# Y-babies_ATtiny84--_PRINT_VER.net
KiCad netlist of a schematic drawn in EAGLE
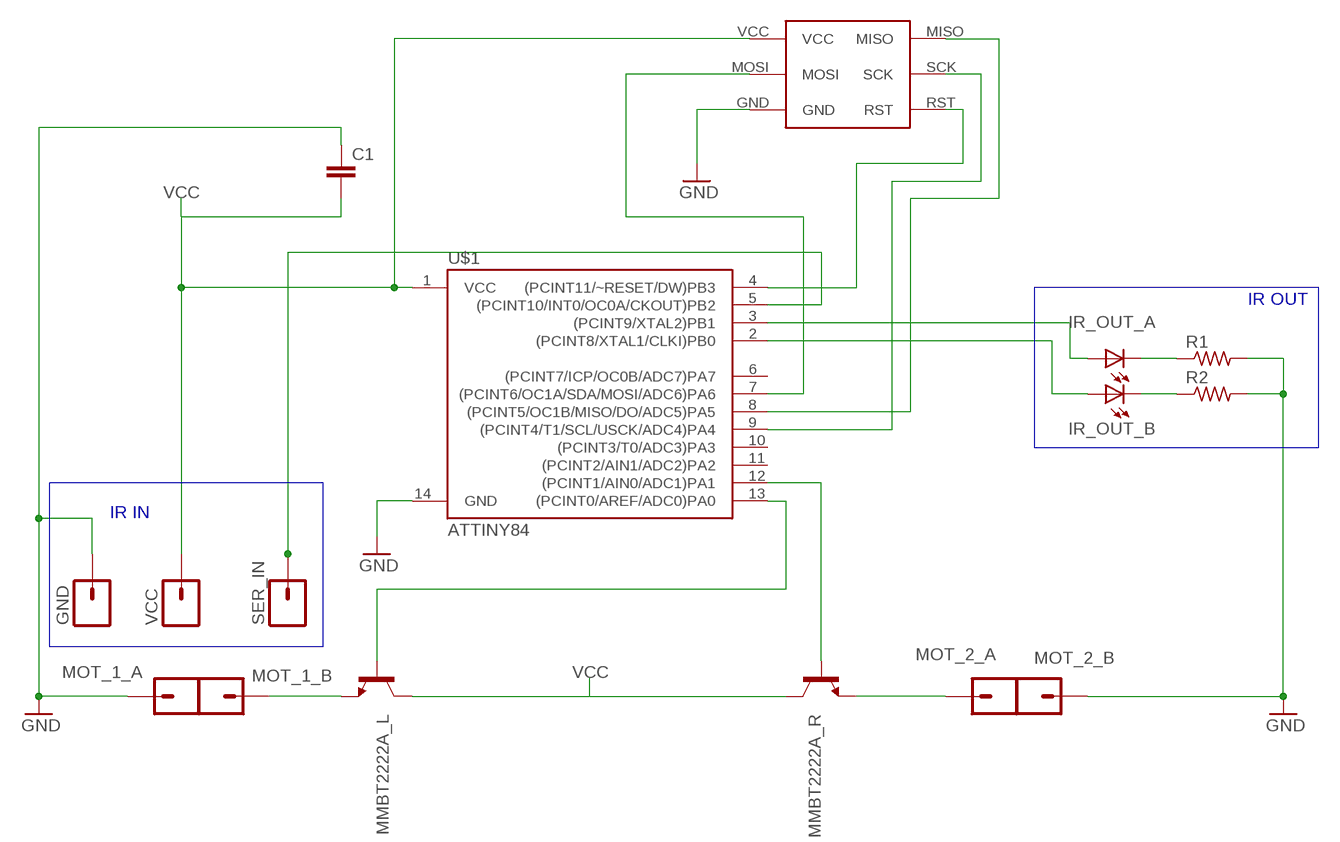
[diagram p0: schematic, sheet 1]

(export (version "E")
  (design (tool "Eeschema 10.0.6"))
  (components
    (comp (ref "C1")
      (value "CAPSMD")
      (footprint "eagle-import:GRM43D")
      (libsource (lib "eagle-import") (part "CAPSMD"))
    )
    (comp (ref "GND")
      (value "M01PTH")
      (footprint "eagle-import:1X01")
      (libsource (lib "eagle-import") (part "M01PTH"))
    )
    (comp (ref "IR_OUT_A")
      (value "LED3MM")
      (footprint "eagle-import:LED3MM")
      (libsource (lib "eagle-import") (part "LED3MM"))
    )
    (comp (ref "IR_OUT_B")
      (value "LED3MM")
      (footprint "eagle-import:LED3MM")
      (libsource (lib "eagle-import") (part "LED3MM"))
    )
    (comp (ref "MMBT2222A_L")
      (value "TRANSISTOR_NPNSOT23")
      (footprint "eagle-import:SOT23")
      (libsource (lib "eagle-import") (part "TRANSISTOR_NPNSOT23"))
    )
    (comp (ref "MMBT2222A_R")
      (value "TRANSISTOR_NPNSOT23")
      (footprint "eagle-import:SOT23")
      (libsource (lib "eagle-import") (part "TRANSISTOR_NPNSOT23"))
    )
    (comp (ref "MOT_1_A")
      (value "M01SMD-4.5X1.5")
      (footprint "eagle-import:PAD-1.5X4.5")
      (libsource (lib "eagle-import") (part "M01SMD-4.5X1.5"))
    )
    (comp (ref "MOT_1_B")
      (value "M01SMD-4.5X1.5")
      (footprint "eagle-import:PAD-1.5X4.5")
      (libsource (lib "eagle-import") (part "M01SMD-4.5X1.5"))
    )
    (comp (ref "MOT_2_A")
      (value "M01SMD-4.5X1.5")
      (footprint "eagle-import:PAD-1.5X4.5")
      (libsource (lib "eagle-import") (part "M01SMD-4.5X1.5"))
    )
    (comp (ref "MOT_2_B")
      (value "M01SMD-4.5X1.5")
      (footprint "eagle-import:PAD-1.5X4.5")
      (libsource (lib "eagle-import") (part "M01SMD-4.5X1.5"))
    )
    (comp (ref "R1")
      (value "R-US_R0805W")
      (footprint "eagle-import:R0805W")
      (libsource (lib "eagle-import") (part "R-US_R0805W"))
    )
    (comp (ref "R2")
      (value "R-US_R0805W")
      (footprint "eagle-import:R0805W")
      (libsource (lib "eagle-import") (part "R-US_R0805W"))
    )
    (comp (ref "SER_IN")
      (value "M01PTH")
      (footprint "eagle-import:1X01")
      (libsource (lib "eagle-import") (part "M01PTH"))
    )
    (comp (ref "U$1")
      (value "ATTINY84")
      (footprint "eagle-import:SO14")
      (libsource (lib "eagle-import") (part "ATTINY84"))
    )
    (comp (ref "U$2")
      (value "POGO_PIN_SPI_PAD")
      (footprint "eagle-import:POGO_PIN_SPI_PAD")
      (libsource (lib "eagle-import") (part "POGO_PIN_SPI_PAD"))
    )
    (comp (ref "VCC")
      (value "M01PTH")
      (footprint "eagle-import:1X01")
      (libsource (lib "eagle-import") (part "M01PTH"))
    )
  )
  (nets
    (net (code "1") (name "/VCC") (class "Default")
      (node (ref "C1") (pin "C") (pinfunction "2_C") (pintype "passive"))
      (node (ref "MMBT2222A_L") (pin "3") (pinfunction "C_3") (pintype "passive"))
      (node (ref "MMBT2222A_R") (pin "3") (pinfunction "C_3") (pintype "passive"))
      (node (ref "U$1") (pin "1") (pinfunction "VCC_1") (pintype "bidirectional"))
      (node (ref "U$2") (pin "VCC") (pinfunction "VCC_VCC") (pintype "bidirectional"))
      (node (ref "VCC") (pin "1") (pinfunction "1_1") (pintype "passive"))
    )
    (net (code "2") (name "GND") (class "Default")
      (node (ref "C1") (pin "A") (pinfunction "1_A") (pintype "passive"))
      (node (ref "GND") (pin "1") (pinfunction "1_1") (pintype "passive"))
      (node (ref "MOT_1_A") (pin "P$1") (pinfunction "1_P$1") (pintype "passive"))
      (node (ref "MOT_2_B") (pin "P$1") (pinfunction "1_P$1") (pintype "passive"))
      (node (ref "R1") (pin "2") (pinfunction "2_2") (pintype "passive"))
      (node (ref "R2") (pin "2") (pinfunction "2_2") (pintype "passive"))
      (node (ref "U$1") (pin "14") (pinfunction "GND_14") (pintype "bidirectional"))
      (node (ref "U$2") (pin "GND") (pinfunction "GND_GND") (pintype "bidirectional"))
    )
    (net (code "3") (name "Net-(IR_OUT_A-C)") (class "Default")
      (node (ref "IR_OUT_A") (pin "K") (pinfunction "C_K") (pintype "passive"))
      (node (ref "R1") (pin "1") (pinfunction "1_1") (pintype "passive"))
    )
    (net (code "4") (name "Net-(IR_OUT_B-C)") (class "Default")
      (node (ref "IR_OUT_B") (pin "K") (pinfunction "C_K") (pintype "passive"))
      (node (ref "R2") (pin "1") (pinfunction "1_1") (pintype "passive"))
    )
    (net (code "5") (name "Net-(MMBT2222A_L-B)") (class "Default")
      (node (ref "MMBT2222A_L") (pin "1") (pinfunction "B_1") (pintype "passive"))
      (node (ref "U$1") (pin "13") (pinfunction "(PCINT0/AREF/ADC0)PA0_13") (pintype "bidirectional"))
    )
    (net (code "6") (name "Net-(MMBT2222A_L-E)") (class "Default")
      (node (ref "MMBT2222A_L") (pin "2") (pinfunction "E_2") (pintype "passive"))
      (node (ref "MOT_1_B") (pin "P$1") (pinfunction "1_P$1") (pintype "passive"))
    )
    (net (code "7") (name "Net-(MMBT2222A_R-B)") (class "Default")
      (node (ref "MMBT2222A_R") (pin "1") (pinfunction "B_1") (pintype "passive"))
      (node (ref "U$1") (pin "12") (pinfunction "(PCINT1/AIN0/ADC1)PA1_12") (pintype "bidirectional"))
    )
    (net (code "8") (name "Net-(MMBT2222A_R-E)") (class "Default")
      (node (ref "MMBT2222A_R") (pin "2") (pinfunction "E_2") (pintype "passive"))
      (node (ref "MOT_2_A") (pin "P$1") (pinfunction "1_P$1") (pintype "passive"))
    )
    (net (code "9") (name "Net-(U$1-(PCINT4{slash}T1{slash}SCL{slash}USCK{slash}ADC4)PA4)") (class "Default")
      (node (ref "U$1") (pin "9") (pinfunction "(PCINT4/T1/SCL/USCK/ADC4)PA4_9") (pintype "bidirectional"))
      (node (ref "U$2") (pin "SCK") (pinfunction "SCK_SCK") (pintype "bidirectional"))
    )
    (net (code "10") (name "Net-(U$1-(PCINT5{slash}OC1B{slash}MISO{slash}DO{slash}ADC5)PA5)") (class "Default")
      (node (ref "U$1") (pin "8") (pinfunction "(PCINT5/OC1B/MISO/DO/ADC5)PA5_8") (pintype "bidirectional"))
      (node (ref "U$2") (pin "MISO") (pinfunction "MISO_MISO") (pintype "bidirectional"))
    )
    (net (code "11") (name "Net-(U$1-(PCINT6{slash}OC1A{slash}SDA{slash}MOSI{slash}ADC6)PA6)") (class "Default")
      (node (ref "U$1") (pin "7") (pinfunction "(PCINT6/OC1A/SDA/MOSI/ADC6)PA6_7") (pintype "bidirectional"))
      (node (ref "U$2") (pin "MOSI") (pinfunction "MOSI_MOSI") (pintype "bidirectional"))
    )
    (net (code "12") (name "Net-(U$1-(PCINT8{slash}XTAL1{slash}CLKI)PB0)") (class "Default")
      (node (ref "IR_OUT_B") (pin "A") (pinfunction "A_A") (pintype "passive"))
      (node (ref "U$1") (pin "2") (pinfunction "(PCINT8/XTAL1/CLKI)PB0_2") (pintype "bidirectional"))
    )
    (net (code "13") (name "Net-(U$1-(PCINT9{slash}XTAL2)PB1)") (class "Default")
      (node (ref "IR_OUT_A") (pin "A") (pinfunction "A_A") (pintype "passive"))
      (node (ref "U$1") (pin "3") (pinfunction "(PCINT9/XTAL2)PB1_3") (pintype "bidirectional"))
    )
    (net (code "14") (name "Net-(U$1-(PCINT10{slash}INT0{slash}OC0A{slash}CKOUT)PB2)") (class "Default")
      (node (ref "SER_IN") (pin "1") (pinfunction "1_1") (pintype "passive"))
      (node (ref "U$1") (pin "5") (pinfunction "(PCINT10/INT0/OC0A/CKOUT)PB2_5") (pintype "bidirectional"))
    )
    (net (code "15") (name "Net-(U$1-(PCINT11{slash}~{RESET{slash}DW})PB3)") (class "Default")
      (node (ref "U$1") (pin "4") (pinfunction "(PCINT11/~{RESET/DW})PB3_4") (pintype "bidirectional"))
      (node (ref "U$2") (pin "RST") (pinfunction "RST_RST") (pintype "bidirectional"))
    )
    (net (code "16") (name "unconnected-(U$1-(PCINT2{slash}AIN1{slash}ADC2)PA2-Pad11)") (class "Default")
      (node (ref "U$1") (pin "11") (pinfunction "(PCINT2/AIN1/ADC2)PA2_11") (pintype "bidirectional"))
    )
    (net (code "17") (name "unconnected-(U$1-(PCINT3{slash}T0{slash}ADC3)PA3-Pad10)") (class "Default")
      (node (ref "U$1") (pin "10") (pinfunction "(PCINT3/T0/ADC3)PA3_10") (pintype "bidirectional"))
    )
    (net (code "18") (name "unconnected-(U$1-(PCINT7{slash}ICP{slash}OC0B{slash}ADC7)PA7-Pad6)") (class "Default")
      (node (ref "U$1") (pin "6") (pinfunction "(PCINT7/ICP/OC0B/ADC7)PA7_6") (pintype "bidirectional"))
    )
  )
)
